# GPS.net
KiCad netlist of a schematic drawn in Altium Designer
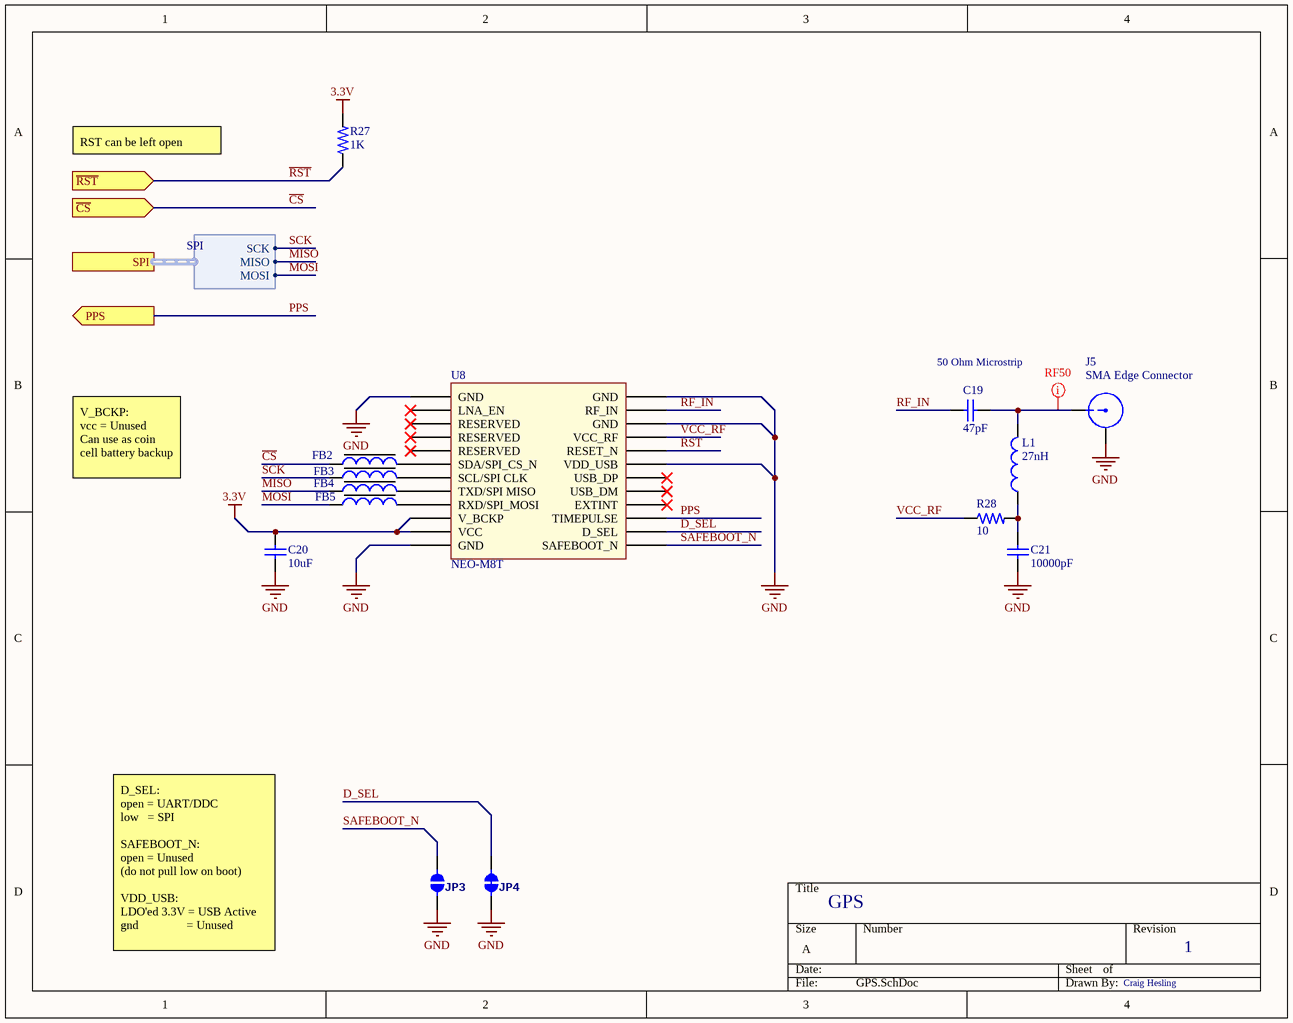
[diagram p0: GPS.SchDoc]

(export (version "E")
  (design (tool "Eeschema 10.0.6"))
  (components
    (comp (ref "C19")
      (value "47pF")
      (footprint "CAPC1608X09L - CAP0603")
      (description "SMT 0603 Ceramic Capacitor")
      (fields (field (name "TOLERANCE") "5%") (field (name "VOLTAGE") "50V"))
      (libsource (lib "Passives") (part "CAP0603 47pF 5% 50V NP0"))
    )
    (comp (ref "C20")
      (value "10uF")
      (footprint "CAPC2013X14L - CAP0805 1.45mm Tall")
      (description "SMT 0805 Ceramic Capacitor")
      (fields (field (name "TOLERANCE") "10%") (field (name "VOLTAGE") "6.3V"))
      (libsource (lib "Passives") (part "CAP0805 10uF 10% 6.3V X5R"))
    )
    (comp (ref "C21")
      (value "10000pF")
      (footprint "CAPC1608X09L - CAP0603")
      (description "SMT 0603 Ceramic Capacitor")
      (fields (field (name "TOLERANCE") "10%") (field (name "VOLTAGE") "50V"))
      (libsource (lib "Passives") (part "CAP0603 10000pF 10% 50V X7R"))
    )
    (comp (ref "FB2")
      (value "Feritte Bead 1kOhm")
      (footprint "FB1608X09L")
      (libsource (lib "Passives") (part "FB0603 1kOhm"))
    )
    (comp (ref "FB3")
      (value "Feritte Bead 1kOhm")
      (footprint "FB1608X09L")
      (libsource (lib "Passives") (part "FB0603 1kOhm"))
    )
    (comp (ref "FB4")
      (value "Feritte Bead 1kOhm")
      (footprint "FB1608X09L")
      (libsource (lib "Passives") (part "FB0603 1kOhm"))
    )
    (comp (ref "FB5")
      (value "Feritte Bead 1kOhm")
      (footprint "FB1608X09L")
      (libsource (lib "Passives") (part "FB0603 1kOhm"))
    )
    (comp (ref "J5")
      (value "SMA Edge Connector")
      (footprint "SMA Connector - Edge Mount Short")
      (libsource (lib "Connectors") (part "SMA Edge Connector"))
    )
    (comp (ref "JP3")
      (value "JUMPER-PAD-2-NO")
      (footprint "PAD-JUMPER-2-NO_NO_SILK")
      (libsource (lib "Passives") (part "JUMPER-PAD-2-NO"))
    )
    (comp (ref "JP4")
      (value "JUMPER-PAD-2-NC_BY_TRACENO_SILK")
      (footprint "PAD-JUMPER-2-NC_BY_TRACE_NO_SILK")
      (libsource (lib "Passives") (part "JUMPER-PAD-2-NC_BY_TRACENO_SILK"))
    )
    (comp (ref "L1")
      (value "27nH")
      (footprint "INDC1608X09L - IND0603 0.95MM TALL")
      (description "SMT 0603 Ceramic Inductor")
      (fields (field (name "TOLERANCE") "5%"))
      (libsource (lib "Passives") (part "IND0603 27nH 400mA 5% 650mOhm 1.7GHz"))
    )
    (comp (ref "R27")
      (value "1K")
      (footprint "RESC1608X06L - RES0603")
      (description "SMT 0603 Ceramic Resistor")
      (fields (field (name "POWER") "1/10W") (field (name "TOLERANCE") "1%"))
      (libsource (lib "Passives") (part "RES0603 1K 1% 1/10W"))
    )
    (comp (ref "R28")
      (value "10")
      (footprint "RESC1608X06L - RES0603")
      (description "SMT 0603 Ceramic Resistor")
      (fields (field (name "POWER") "1/10W") (field (name "TOLERANCE") "1%"))
      (libsource (lib "Passives") (part "RES0603 10 1% 1/10W"))
    )
    (comp (ref "U8")
      (value "NEO-M8T")
      (footprint "NEO")
      (description "u-blox NEO GNSS module")
      (fields (field (name "MANUFACTURER") "u-blox"))
      (libsource (lib "ubloxLib") (part "NEO"))
    )
  )
  (nets
    (net (code "2") (name "/D_SEL") (class "Default")
      (node (ref "JP4") (pin "2") (pinfunction "2_2") (pintype "passive"))
      (node (ref "U8") (pin "2") (pinfunction "D_SEL_2") (pintype "passive"))
    )
    (net (code "3") (name "/MISO") (class "Default")
      (node (ref "FB4") (pin "1") (pinfunction "1_1") (pintype "passive"))
    )
    (net (code "4") (name "/MOSI") (class "Default")
      (node (ref "FB5") (pin "1") (pinfunction "1_1") (pintype "passive"))
    )
    (net (code "5") (name "/PPS") (class "Default")
      (node (ref "U8") (pin "3") (pinfunction "TIMEPULSE_3") (pintype "passive"))
    )
    (net (code "6") (name "/RF_IN") (class "Default")
      (node (ref "C19") (pin "1") (pinfunction "1_1") (pintype "passive"))
      (node (ref "U8") (pin "11") (pinfunction "RF_IN_11") (pintype "passive"))
    )
    (net (code "7") (name "/SAFEBOOT_N") (class "Default")
      (node (ref "JP3") (pin "2") (pinfunction "2_2") (pintype "passive"))
      (node (ref "U8") (pin "1") (pinfunction "SAFEBOOT_N_1") (pintype "passive"))
    )
    (net (code "8") (name "/SCK") (class "Default")
      (node (ref "FB3") (pin "1") (pinfunction "1_1") (pintype "passive"))
    )
    (net (code "9") (name "/VCC_RF") (class "Default")
      (node (ref "R28") (pin "1") (pinfunction "1_1") (pintype "passive"))
      (node (ref "U8") (pin "9") (pinfunction "VCC_RF_9") (pintype "passive"))
    )
    (net (code "11") (name "/~{CS}") (class "Default")
      (node (ref "FB2") (pin "1") (pinfunction "1_1") (pintype "passive"))
    )
    (net (code "12") (name "/~{RST}") (class "Default")
      (node (ref "R27") (pin "1") (pinfunction "1_1") (pintype "passive"))
      (node (ref "U8") (pin "8") (pinfunction "RESET_N_8") (pintype "passive"))
    )
    (net (code "13") (name "3.3V") (class "Default")
      (node (ref "C20") (pin "2") (pinfunction "2_2") (pintype "passive"))
      (node (ref "R27") (pin "2") (pinfunction "2_2") (pintype "passive"))
      (node (ref "U8") (pin "22") (pinfunction "V_BCKP_22") (pintype "passive"))
      (node (ref "U8") (pin "23") (pinfunction "VCC_23") (pintype "passive"))
    )
    (net (code "14") (name "GND") (class "Default")
      (node (ref "C20") (pin "1") (pinfunction "1_1") (pintype "passive"))
      (node (ref "C21") (pin "1") (pinfunction "1_1") (pintype "passive"))
      (node (ref "J5") (pin "2") (pinfunction "GND_2") (pintype "passive"))
      (node (ref "JP3") (pin "1") (pinfunction "1_1") (pintype "passive"))
      (node (ref "JP4") (pin "1") (pinfunction "1_1") (pintype "passive"))
      (node (ref "U8") (pin "10") (pinfunction "GND_10") (pintype "passive"))
      (node (ref "U8") (pin "12") (pinfunction "GND_12") (pintype "passive"))
      (node (ref "U8") (pin "13") (pinfunction "GND_13") (pintype "passive"))
      (node (ref "U8") (pin "24") (pinfunction "GND_24") (pintype "passive"))
      (node (ref "U8") (pin "7") (pinfunction "VDD_USB_7") (pintype "passive"))
    )
    (net (code "15") (name "Net-(C21-Pad2)") (class "Default")
      (node (ref "C21") (pin "2") (pinfunction "2_2") (pintype "passive"))
      (node (ref "L1") (pin "1") (pinfunction "1_1") (pintype "passive"))
      (node (ref "R28") (pin "2") (pinfunction "2_2") (pintype "passive"))
    )
    (net (code "16") (name "Net-(J5-Signal)") (class "Default")
      (node (ref "C19") (pin "2") (pinfunction "2_2") (pintype "passive"))
      (node (ref "J5") (pin "1") (pinfunction "Signal_1") (pintype "passive"))
      (node (ref "L1") (pin "2") (pinfunction "2_2") (pintype "passive"))
    )
    (net (code "17") (name "Net-(U8-RXD{slash}SPI_MOSI)") (class "Default")
      (node (ref "FB5") (pin "2") (pinfunction "2_2") (pintype "passive"))
      (node (ref "U8") (pin "21") (pinfunction "RXD/SPI_MOSI_21") (pintype "passive"))
    )
    (net (code "18") (name "Net-(U8-SCL{slash}SPI_CLK)") (class "Default")
      (node (ref "FB3") (pin "2") (pinfunction "2_2") (pintype "passive"))
      (node (ref "U8") (pin "19") (pinfunction "SCL/SPI_CLK_19") (pintype "passive"))
    )
    (net (code "19") (name "Net-(U8-SDA{slash}SPI_CS_N)") (class "Default")
      (node (ref "FB2") (pin "2") (pinfunction "2_2") (pintype "passive"))
      (node (ref "U8") (pin "18") (pinfunction "SDA/SPI_CS_N_18") (pintype "passive"))
    )
    (net (code "20") (name "Net-(U8-TXD{slash}SPI_MISO)") (class "Default")
      (node (ref "FB4") (pin "2") (pinfunction "2_2") (pintype "passive"))
      (node (ref "U8") (pin "20") (pinfunction "TXD/SPI_MISO_20") (pintype "passive"))
    )
    (net (code "21") (name "unconnected-(U8-EXTINT-Pad4)") (class "Default")
      (node (ref "U8") (pin "4") (pinfunction "EXTINT_4") (pintype "passive+no_connect"))
    )
    (net (code "22") (name "unconnected-(U8-LNA_EN-Pad14)") (class "Default")
      (node (ref "U8") (pin "14") (pinfunction "LNA_EN_14") (pintype "passive+no_connect"))
    )
    (net (code "23") (name "unconnected-(U8-RESERVED-Pad15)") (class "Default")
      (node (ref "U8") (pin "15") (pinfunction "RESERVED_15") (pintype "passive+no_connect"))
    )
    (net (code "24") (name "unconnected-(U8-RESERVED-Pad16)") (class "Default")
      (node (ref "U8") (pin "16") (pinfunction "RESERVED_16") (pintype "passive+no_connect"))
    )
    (net (code "25") (name "unconnected-(U8-RESERVED-Pad17)") (class "Default")
      (node (ref "U8") (pin "17") (pinfunction "RESERVED_17") (pintype "passive+no_connect"))
    )
    (net (code "26") (name "unconnected-(U8-USB_DM-Pad5)") (class "Default")
      (node (ref "U8") (pin "5") (pinfunction "USB_DM_5") (pintype "passive+no_connect"))
    )
    (net (code "27") (name "unconnected-(U8-USB_DP-Pad6)") (class "Default")
      (node (ref "U8") (pin "6") (pinfunction "USB_DP_6") (pintype "passive+no_connect"))
    )
  )
)
